# Receiver_Schematic_Visualization.net
KiCad netlist of a schematic drawn in EAGLE
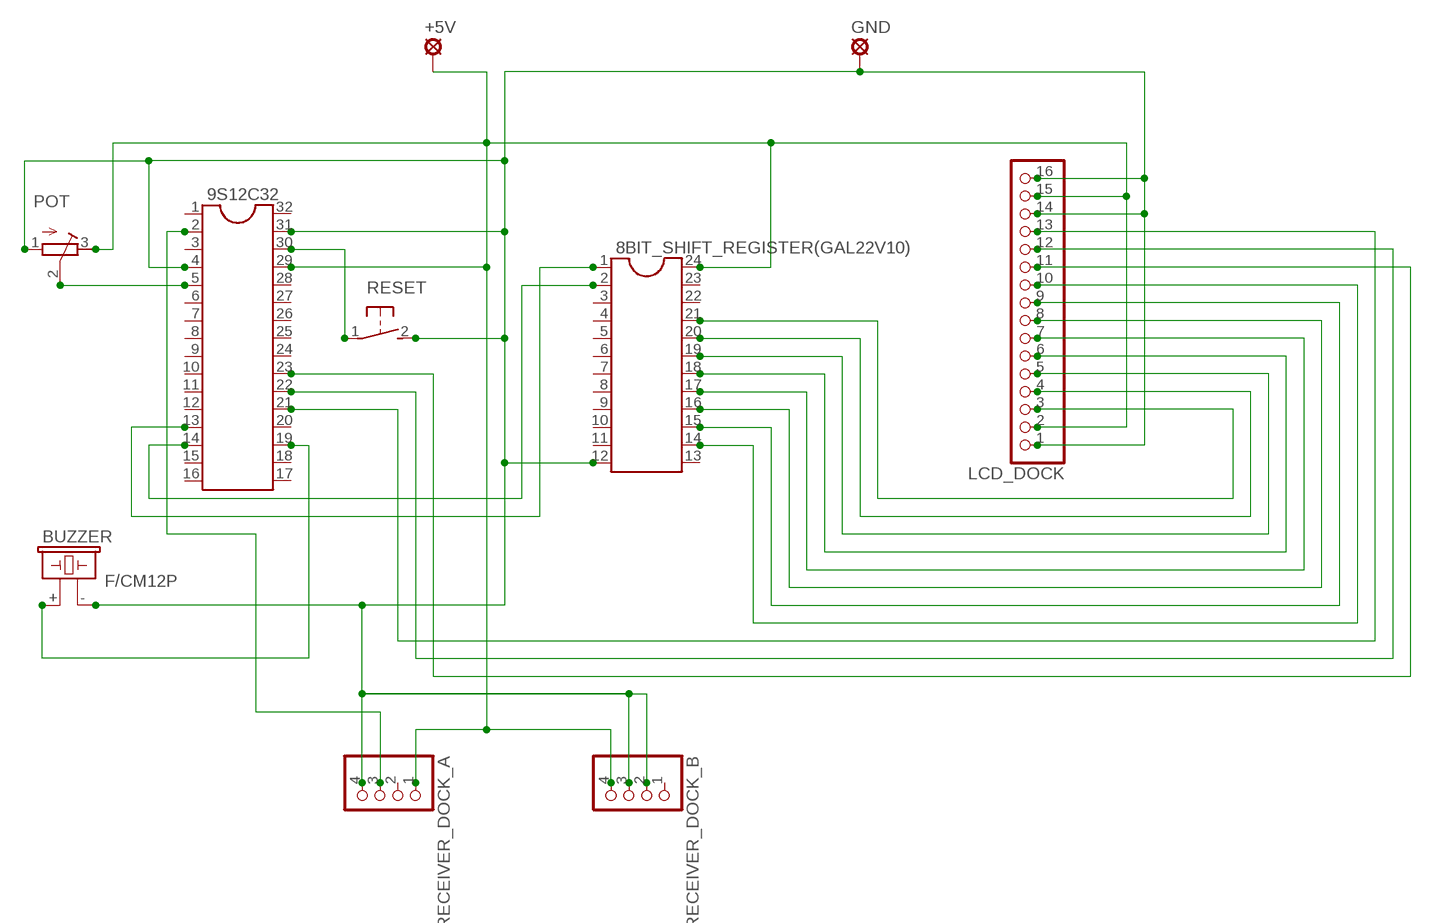
[diagram p0: schematic, sheet 1]

(export (version "E")
  (design (tool "Eeschema 10.0.6"))
  (components
    (comp (ref "+5V")
      (value "LSP10")
      (footprint "eagle-import:LSP10")
      (libsource (lib "eagle-import") (part "LSP10"))
    )
    (comp (ref "8BIT_SHIFT_REGISTER(GAL22V10)")
      (value "DIL24-6")
      (footprint "eagle-import:DIL24-6")
      (libsource (lib "eagle-import") (part "DIL24-6"))
    )
    (comp (ref "9S12C32")
      (value "DIL32")
      (footprint "eagle-import:DIL32")
      (libsource (lib "eagle-import") (part "DIL32"))
    )
    (comp (ref "BUZZER")
      (value "F/CM12P")
      (footprint "eagle-import:F_CM12P")
      (libsource (lib "eagle-import") (part "F/CM12P"))
    )
    (comp (ref "GND")
      (value "LSP10")
      (footprint "eagle-import:LSP10")
      (libsource (lib "eagle-import") (part "LSP10"))
    )
    (comp (ref "LCD_DOCK")
      (value "PINHD-1X16/90")
      (footprint "eagle-import:1X16_90")
      (libsource (lib "eagle-import") (part "PINHD-1X16/90"))
    )
    (comp (ref "POT")
      (value "R-TRIMM3296X")
      (footprint "eagle-import:RTRIM3296X")
      (libsource (lib "eagle-import") (part "R-TRIMM3296X"))
    )
    (comp (ref "RECEIVER_DOCK_A")
      (value "PINHD-1X4/90")
      (footprint "eagle-import:1X04_90")
      (libsource (lib "eagle-import") (part "PINHD-1X4/90"))
    )
    (comp (ref "RECEIVER_DOCK_B")
      (value "PINHD-1X4/90")
      (footprint "eagle-import:1X04_90")
      (libsource (lib "eagle-import") (part "PINHD-1X4/90"))
    )
    (comp (ref "RESET")
      (value "31-XX")
      (footprint "eagle-import:B3F-31XX")
      (fields (field (name "MPN") "B3F-3100"))
      (libsource (lib "eagle-import") (part "31-XX"))
    )
  )
  (nets
    (net (code "1") (name "Net-(8BIT_SHIFT_REGISTER(GAL22V10)-Pad1)") (class "Default")
      (node (ref "8BIT_SHIFT_REGISTER(GAL22V10)") (pin "1") (pinfunction "1_1") (pintype "passive"))
      (node (ref "9S12C32") (pin "13") (pinfunction "13_13") (pintype "passive"))
    )
    (net (code "2") (name "Net-(8BIT_SHIFT_REGISTER(GAL22V10)-Pad2)") (class "Default")
      (node (ref "8BIT_SHIFT_REGISTER(GAL22V10)") (pin "2") (pinfunction "2_2") (pintype "passive"))
      (node (ref "9S12C32") (pin "14") (pinfunction "14_14") (pintype "passive"))
    )
    (net (code "3") (name "Net-(8BIT_SHIFT_REGISTER(GAL22V10)-Pad14)") (class "Default")
      (node (ref "8BIT_SHIFT_REGISTER(GAL22V10)") (pin "14") (pinfunction "14_14") (pintype "passive"))
      (node (ref "LCD_DOCK") (pin "10") (pinfunction "10_10") (pintype "passive"))
    )
    (net (code "4") (name "Net-(8BIT_SHIFT_REGISTER(GAL22V10)-Pad15)") (class "Default")
      (node (ref "8BIT_SHIFT_REGISTER(GAL22V10)") (pin "15") (pinfunction "15_15") (pintype "passive"))
      (node (ref "LCD_DOCK") (pin "9") (pinfunction "9_9") (pintype "passive"))
    )
    (net (code "5") (name "Net-(8BIT_SHIFT_REGISTER(GAL22V10)-Pad16)") (class "Default")
      (node (ref "8BIT_SHIFT_REGISTER(GAL22V10)") (pin "16") (pinfunction "16_16") (pintype "passive"))
      (node (ref "LCD_DOCK") (pin "8") (pinfunction "8_8") (pintype "passive"))
    )
    (net (code "6") (name "Net-(8BIT_SHIFT_REGISTER(GAL22V10)-Pad17)") (class "Default")
      (node (ref "8BIT_SHIFT_REGISTER(GAL22V10)") (pin "17") (pinfunction "17_17") (pintype "passive"))
      (node (ref "LCD_DOCK") (pin "7") (pinfunction "7_7") (pintype "passive"))
    )
    (net (code "7") (name "Net-(8BIT_SHIFT_REGISTER(GAL22V10)-Pad18)") (class "Default")
      (node (ref "8BIT_SHIFT_REGISTER(GAL22V10)") (pin "18") (pinfunction "18_18") (pintype "passive"))
      (node (ref "LCD_DOCK") (pin "6") (pinfunction "6_6") (pintype "passive"))
    )
    (net (code "8") (name "Net-(8BIT_SHIFT_REGISTER(GAL22V10)-Pad19)") (class "Default")
      (node (ref "8BIT_SHIFT_REGISTER(GAL22V10)") (pin "19") (pinfunction "19_19") (pintype "passive"))
      (node (ref "LCD_DOCK") (pin "5") (pinfunction "5_5") (pintype "passive"))
    )
    (net (code "9") (name "Net-(8BIT_SHIFT_REGISTER(GAL22V10)-Pad20)") (class "Default")
      (node (ref "8BIT_SHIFT_REGISTER(GAL22V10)") (pin "20") (pinfunction "20_20") (pintype "passive"))
      (node (ref "LCD_DOCK") (pin "4") (pinfunction "4_4") (pintype "passive"))
    )
    (net (code "10") (name "Net-(8BIT_SHIFT_REGISTER(GAL22V10)-Pad21)") (class "Default")
      (node (ref "8BIT_SHIFT_REGISTER(GAL22V10)") (pin "21") (pinfunction "21_21") (pintype "passive"))
      (node (ref "LCD_DOCK") (pin "3") (pinfunction "3_3") (pintype "passive"))
    )
    (net (code "11") (name "Net-(9S12C32-Pad2)") (class "Default")
      (node (ref "9S12C32") (pin "2") (pinfunction "2_2") (pintype "passive"))
      (node (ref "RECEIVER_DOCK_A") (pin "3") (pinfunction "3_3") (pintype "passive"))
    )
    (net (code "12") (name "Net-(9S12C32-Pad21)") (class "Default")
      (node (ref "9S12C32") (pin "21") (pinfunction "21_21") (pintype "passive"))
      (node (ref "LCD_DOCK") (pin "13") (pinfunction "13_13") (pintype "passive"))
    )
    (net (code "13") (name "Net-(9S12C32-Pad22)") (class "Default")
      (node (ref "9S12C32") (pin "22") (pinfunction "22_22") (pintype "passive"))
      (node (ref "LCD_DOCK") (pin "12") (pinfunction "12_12") (pintype "passive"))
    )
    (net (code "14") (name "Net-(9S12C32-Pad23)") (class "Default")
      (node (ref "9S12C32") (pin "23") (pinfunction "23_23") (pintype "passive"))
      (node (ref "LCD_DOCK") (pin "11") (pinfunction "11_11") (pintype "passive"))
    )
    (net (code "15") (name "Net-(BUZZER-1)") (class "Default")
      (node (ref "9S12C32") (pin "19") (pinfunction "19_19") (pintype "passive"))
      (node (ref "BUZZER") (pin "+") (pinfunction "1_+") (pintype "passive"))
    )
    (net (code "16") (name "Net-(BUZZER-2)") (class "Default")
      (node (ref "8BIT_SHIFT_REGISTER(GAL22V10)") (pin "12") (pinfunction "12_12") (pintype "passive"))
      (node (ref "9S12C32") (pin "31") (pinfunction "31_31") (pintype "passive"))
      (node (ref "9S12C32") (pin "4") (pinfunction "4_4") (pintype "passive"))
      (node (ref "BUZZER") (pin "-") (pinfunction "2_-") (pintype "passive"))
      (node (ref "GND") (pin "MP") (pinfunction "MP_MP") (pintype "passive"))
      (node (ref "LCD_DOCK") (pin "1") (pinfunction "1_1") (pintype "passive"))
      (node (ref "LCD_DOCK") (pin "14") (pinfunction "14_14") (pintype "passive"))
      (node (ref "LCD_DOCK") (pin "16") (pinfunction "16_16") (pintype "passive"))
      (node (ref "POT") (pin "1") (pinfunction "E_1") (pintype "passive"))
      (node (ref "RECEIVER_DOCK_A") (pin "4") (pinfunction "4_4") (pintype "passive"))
      (node (ref "RECEIVER_DOCK_B") (pin "2") (pinfunction "2_2") (pintype "passive"))
      (node (ref "RECEIVER_DOCK_B") (pin "3") (pinfunction "3_3") (pintype "passive"))
      (node (ref "RESET") (pin "2") (pinfunction "S_2") (pintype "passive"))
    )
    (net (code "17") (name "Net-(POT-A)") (class "Default")
      (node (ref "+5V") (pin "MP") (pinfunction "MP_MP") (pintype "passive"))
      (node (ref "8BIT_SHIFT_REGISTER(GAL22V10)") (pin "24") (pinfunction "24_24") (pintype "passive"))
      (node (ref "9S12C32") (pin "29") (pinfunction "29_29") (pintype "passive"))
      (node (ref "LCD_DOCK") (pin "15") (pinfunction "15_15") (pintype "passive"))
      (node (ref "LCD_DOCK") (pin "2") (pinfunction "2_2") (pintype "passive"))
      (node (ref "POT") (pin "3") (pinfunction "A_3") (pintype "passive"))
      (node (ref "RECEIVER_DOCK_A") (pin "1") (pinfunction "1_1") (pintype "passive"))
      (node (ref "RECEIVER_DOCK_B") (pin "4") (pinfunction "4_4") (pintype "passive"))
    )
    (net (code "18") (name "Net-(POT-S)") (class "Default")
      (node (ref "9S12C32") (pin "5") (pinfunction "5_5") (pintype "passive"))
      (node (ref "POT") (pin "2") (pinfunction "S_2") (pintype "passive"))
    )
    (net (code "19") (name "Net-(RESET-P)") (class "Default")
      (node (ref "9S12C32") (pin "30") (pinfunction "30_30") (pintype "passive"))
      (node (ref "RESET") (pin "1") (pinfunction "P_1") (pintype "passive"))
    )
    (net (code "20") (name "unconnected-(8BIT_SHIFT_REGISTER(GAL22V10)-Pad3)") (class "Default")
      (node (ref "8BIT_SHIFT_REGISTER(GAL22V10)") (pin "3") (pinfunction "3_3") (pintype "passive"))
    )
    (net (code "21") (name "unconnected-(8BIT_SHIFT_REGISTER(GAL22V10)-Pad4)") (class "Default")
      (node (ref "8BIT_SHIFT_REGISTER(GAL22V10)") (pin "4") (pinfunction "4_4") (pintype "passive"))
    )
    (net (code "22") (name "unconnected-(8BIT_SHIFT_REGISTER(GAL22V10)-Pad5)") (class "Default")
      (node (ref "8BIT_SHIFT_REGISTER(GAL22V10)") (pin "5") (pinfunction "5_5") (pintype "passive"))
    )
    (net (code "23") (name "unconnected-(8BIT_SHIFT_REGISTER(GAL22V10)-Pad6)") (class "Default")
      (node (ref "8BIT_SHIFT_REGISTER(GAL22V10)") (pin "6") (pinfunction "6_6") (pintype "passive"))
    )
    (net (code "24") (name "unconnected-(8BIT_SHIFT_REGISTER(GAL22V10)-Pad7)") (class "Default")
      (node (ref "8BIT_SHIFT_REGISTER(GAL22V10)") (pin "7") (pinfunction "7_7") (pintype "passive"))
    )
    (net (code "25") (name "unconnected-(8BIT_SHIFT_REGISTER(GAL22V10)-Pad8)") (class "Default")
      (node (ref "8BIT_SHIFT_REGISTER(GAL22V10)") (pin "8") (pinfunction "8_8") (pintype "passive"))
    )
    (net (code "26") (name "unconnected-(8BIT_SHIFT_REGISTER(GAL22V10)-Pad9)") (class "Default")
      (node (ref "8BIT_SHIFT_REGISTER(GAL22V10)") (pin "9") (pinfunction "9_9") (pintype "passive"))
    )
    (net (code "27") (name "unconnected-(8BIT_SHIFT_REGISTER(GAL22V10)-Pad10)") (class "Default")
      (node (ref "8BIT_SHIFT_REGISTER(GAL22V10)") (pin "10") (pinfunction "10_10") (pintype "passive"))
    )
    (net (code "28") (name "unconnected-(8BIT_SHIFT_REGISTER(GAL22V10)-Pad11)") (class "Default")
      (node (ref "8BIT_SHIFT_REGISTER(GAL22V10)") (pin "11") (pinfunction "11_11") (pintype "passive"))
    )
    (net (code "29") (name "unconnected-(8BIT_SHIFT_REGISTER(GAL22V10)-Pad13)") (class "Default")
      (node (ref "8BIT_SHIFT_REGISTER(GAL22V10)") (pin "13") (pinfunction "13_13") (pintype "passive"))
    )
    (net (code "30") (name "unconnected-(8BIT_SHIFT_REGISTER(GAL22V10)-Pad22)") (class "Default")
      (node (ref "8BIT_SHIFT_REGISTER(GAL22V10)") (pin "22") (pinfunction "22_22") (pintype "passive"))
    )
    (net (code "31") (name "unconnected-(8BIT_SHIFT_REGISTER(GAL22V10)-Pad23)") (class "Default")
      (node (ref "8BIT_SHIFT_REGISTER(GAL22V10)") (pin "23") (pinfunction "23_23") (pintype "passive"))
    )
    (net (code "32") (name "unconnected-(9S12C32-Pad1)") (class "Default")
      (node (ref "9S12C32") (pin "1") (pinfunction "1_1") (pintype "passive"))
    )
    (net (code "33") (name "unconnected-(9S12C32-Pad3)") (class "Default")
      (node (ref "9S12C32") (pin "3") (pinfunction "3_3") (pintype "passive"))
    )
    (net (code "34") (name "unconnected-(9S12C32-Pad6)") (class "Default")
      (node (ref "9S12C32") (pin "6") (pinfunction "6_6") (pintype "passive"))
    )
    (net (code "35") (name "unconnected-(9S12C32-Pad7)") (class "Default")
      (node (ref "9S12C32") (pin "7") (pinfunction "7_7") (pintype "passive"))
    )
    (net (code "36") (name "unconnected-(9S12C32-Pad8)") (class "Default")
      (node (ref "9S12C32") (pin "8") (pinfunction "8_8") (pintype "passive"))
    )
    (net (code "37") (name "unconnected-(9S12C32-Pad9)") (class "Default")
      (node (ref "9S12C32") (pin "9") (pinfunction "9_9") (pintype "passive"))
    )
    (net (code "38") (name "unconnected-(9S12C32-Pad10)") (class "Default")
      (node (ref "9S12C32") (pin "10") (pinfunction "10_10") (pintype "passive"))
    )
    (net (code "39") (name "unconnected-(9S12C32-Pad11)") (class "Default")
      (node (ref "9S12C32") (pin "11") (pinfunction "11_11") (pintype "passive"))
    )
    (net (code "40") (name "unconnected-(9S12C32-Pad12)") (class "Default")
      (node (ref "9S12C32") (pin "12") (pinfunction "12_12") (pintype "passive"))
    )
    (net (code "41") (name "unconnected-(9S12C32-Pad15)") (class "Default")
      (node (ref "9S12C32") (pin "15") (pinfunction "15_15") (pintype "passive"))
    )
    (net (code "42") (name "unconnected-(9S12C32-Pad16)") (class "Default")
      (node (ref "9S12C32") (pin "16") (pinfunction "16_16") (pintype "passive"))
    )
    (net (code "43") (name "unconnected-(9S12C32-Pad17)") (class "Default")
      (node (ref "9S12C32") (pin "17") (pinfunction "17_17") (pintype "passive"))
    )
    (net (code "44") (name "unconnected-(9S12C32-Pad18)") (class "Default")
      (node (ref "9S12C32") (pin "18") (pinfunction "18_18") (pintype "passive"))
    )
    (net (code "45") (name "unconnected-(9S12C32-Pad20)") (class "Default")
      (node (ref "9S12C32") (pin "20") (pinfunction "20_20") (pintype "passive"))
    )
    (net (code "46") (name "unconnected-(9S12C32-Pad24)") (class "Default")
      (node (ref "9S12C32") (pin "24") (pinfunction "24_24") (pintype "passive"))
    )
    (net (code "47") (name "unconnected-(9S12C32-Pad25)") (class "Default")
      (node (ref "9S12C32") (pin "25") (pinfunction "25_25") (pintype "passive"))
    )
    (net (code "48") (name "unconnected-(9S12C32-Pad26)") (class "Default")
      (node (ref "9S12C32") (pin "26") (pinfunction "26_26") (pintype "passive"))
    )
    (net (code "49") (name "unconnected-(9S12C32-Pad27)") (class "Default")
      (node (ref "9S12C32") (pin "27") (pinfunction "27_27") (pintype "passive"))
    )
    (net (code "50") (name "unconnected-(9S12C32-Pad28)") (class "Default")
      (node (ref "9S12C32") (pin "28") (pinfunction "28_28") (pintype "passive"))
    )
    (net (code "51") (name "unconnected-(9S12C32-Pad32)") (class "Default")
      (node (ref "9S12C32") (pin "32") (pinfunction "32_32") (pintype "passive"))
    )
    (net (code "52") (name "unconnected-(RECEIVER_DOCK_A-Pad2)") (class "Default")
      (node (ref "RECEIVER_DOCK_A") (pin "2") (pinfunction "2_2") (pintype "passive"))
    )
    (net (code "53") (name "unconnected-(RECEIVER_DOCK_B-Pad1)") (class "Default")
      (node (ref "RECEIVER_DOCK_B") (pin "1") (pinfunction "1_1") (pintype "passive"))
    )
  )
)
